# MCU.net
KiCad netlist of a schematic drawn in Altium Designer
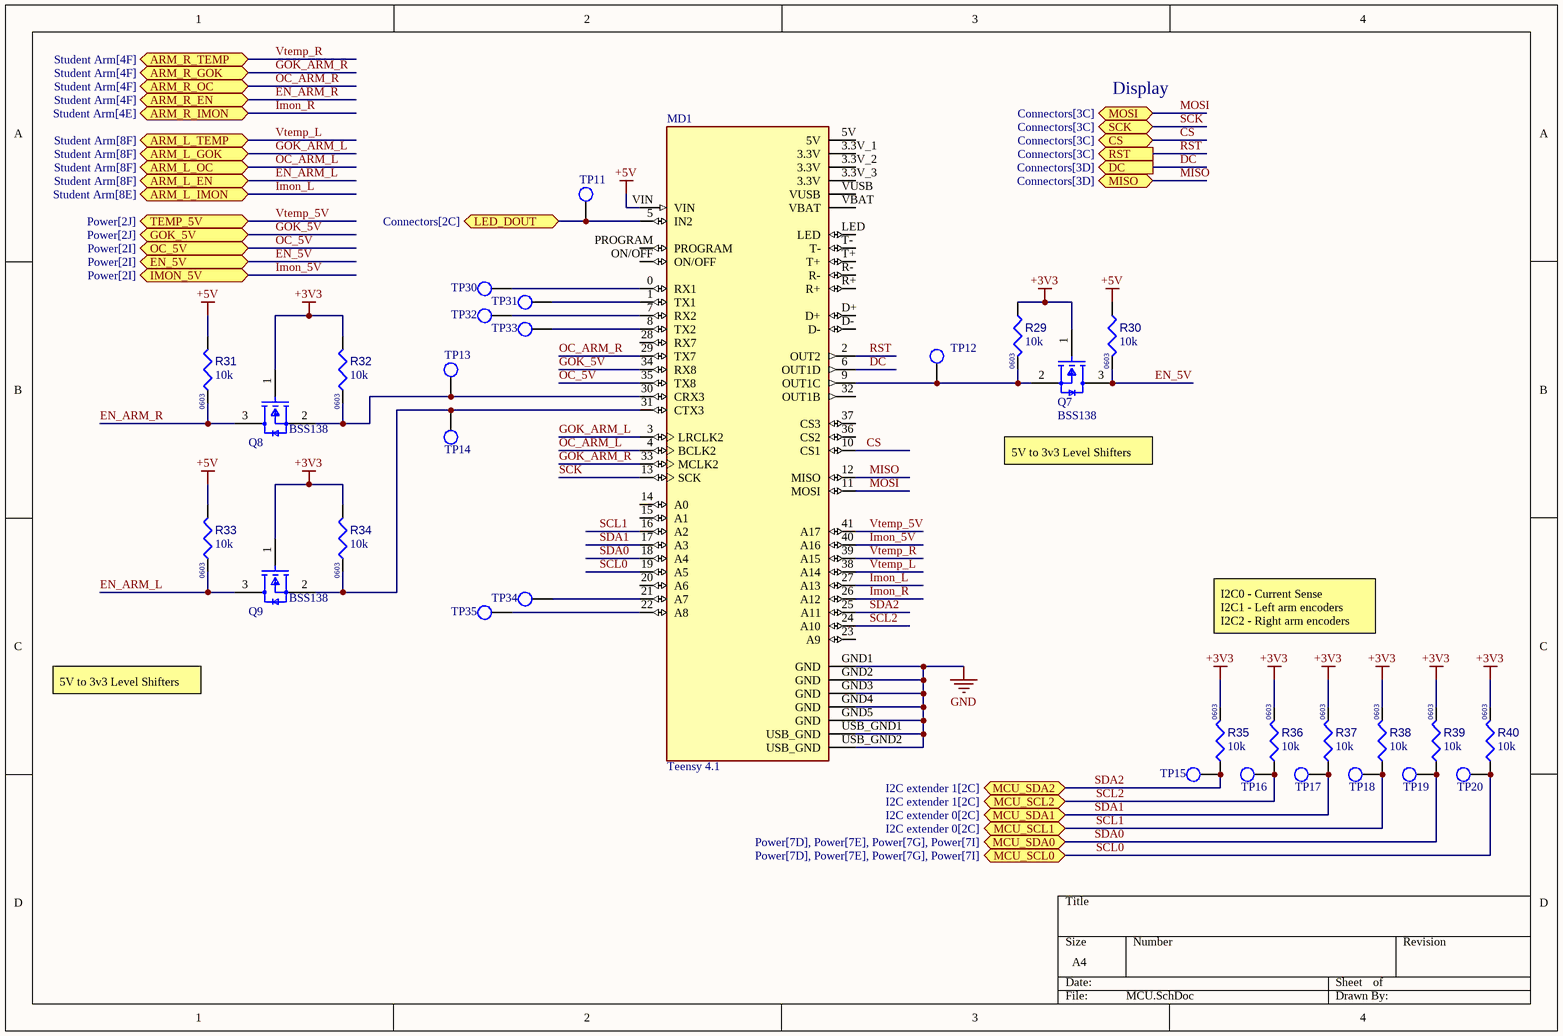
[diagram p0: MCU.SchDoc]

(export (version "E")
  (design (tool "Eeschema 10.0.6"))
  (components
    (comp (ref "MD1")
      (value "Teensy 4.1")
      (footprint "FP-DEV-16771-MFG")
      (description "iMXRT1062 Microcontroller Development Board 600MHz CPU 1GB RAM 8MB Flash")
      (libsource (lib "hawaiirobotics") (part "db1e865d41383118ef0d77a6dfc77c5"))
    )
    (comp (ref "Q7")
      (value "BSS138")
      (footprint "FP-318-08-IPC_B")
      (description "MOSFET N-CH 50V 220MA SOT-23")
      (libsource (lib "Altium Content Vault") (part "3b9c635fedb024a5347a57b145af9cc"))
    )
    (comp (ref "Q8")
      (value "BSS138")
      (footprint "FP-318-08-IPC_B")
      (description "MOSFET N-CH 50V 220MA SOT-23")
      (libsource (lib "Altium Content Vault") (part "3b9c635fedb024a5347a57b145af9cc"))
    )
    (comp (ref "Q9")
      (value "BSS138")
      (footprint "FP-318-08-IPC_B")
      (description "MOSFET N-CH 50V 220MA SOT-23")
      (libsource (lib "Altium Content Vault") (part "3b9c635fedb024a5347a57b145af9cc"))
    )
    (comp (ref "R29")
      (value "10k")
      (footprint "RESC1608X55X25NL10T15")
      (description "Chip Resistor, 10 KOhm, +/- 1%, 01 W, -55 to 155 degC, 0603 (1608 Metric)")
      (fields
        (field (name "CASE/PACKAGE") "0603")
        (field (name "POWER") "100mW")
        (field (name "TOLERANCE") "1%")
      )
      (libsource (lib "hawaiirobotics") (part "RES-2"))
    )
    (comp (ref "R30")
      (value "10k")
      (footprint "RESC1608X55X25NL10T15")
      (description "Chip Resistor, 10 KOhm, +/- 1%, 01 W, -55 to 155 degC, 0603 (1608 Metric)")
      (fields
        (field (name "CASE/PACKAGE") "0603")
        (field (name "POWER") "100mW")
        (field (name "TOLERANCE") "1%")
      )
      (libsource (lib "hawaiirobotics") (part "RES-2"))
    )
    (comp (ref "R31")
      (value "10k")
      (footprint "RESC1608X55X25NL10T15")
      (description "Chip Resistor, 10 KOhm, +/- 1%, 01 W, -55 to 155 degC, 0603 (1608 Metric)")
      (fields
        (field (name "CASE/PACKAGE") "0603")
        (field (name "POWER") "100mW")
        (field (name "TOLERANCE") "1%")
      )
      (libsource (lib "hawaiirobotics") (part "RES-2"))
    )
    (comp (ref "R32")
      (value "10k")
      (footprint "RESC1608X55X25NL10T15")
      (description "Chip Resistor, 10 KOhm, +/- 1%, 01 W, -55 to 155 degC, 0603 (1608 Metric)")
      (fields
        (field (name "CASE/PACKAGE") "0603")
        (field (name "POWER") "100mW")
        (field (name "TOLERANCE") "1%")
      )
      (libsource (lib "hawaiirobotics") (part "RES-2"))
    )
    (comp (ref "R33")
      (value "10k")
      (footprint "RESC1608X55X25NL10T15")
      (description "Chip Resistor, 10 KOhm, +/- 1%, 01 W, -55 to 155 degC, 0603 (1608 Metric)")
      (fields
        (field (name "CASE/PACKAGE") "0603")
        (field (name "POWER") "100mW")
        (field (name "TOLERANCE") "1%")
      )
      (libsource (lib "hawaiirobotics") (part "RES-2"))
    )
    (comp (ref "R34")
      (value "10k")
      (footprint "RESC1608X55X25NL10T15")
      (description "Chip Resistor, 10 KOhm, +/- 1%, 01 W, -55 to 155 degC, 0603 (1608 Metric)")
      (fields
        (field (name "CASE/PACKAGE") "0603")
        (field (name "POWER") "100mW")
        (field (name "TOLERANCE") "1%")
      )
      (libsource (lib "hawaiirobotics") (part "RES-2"))
    )
    (comp (ref "R35")
      (value "10k")
      (footprint "RESC1608X55X25NL10T15")
      (description "Chip Resistor, 10 KOhm, +/- 1%, 01 W, -55 to 155 degC, 0603 (1608 Metric)")
      (fields
        (field (name "CASE/PACKAGE") "0603")
        (field (name "POWER") "100mW")
        (field (name "TOLERANCE") "1%")
      )
      (libsource (lib "hawaiirobotics") (part "RES-2"))
    )
    (comp (ref "R36")
      (value "10k")
      (footprint "RESC1608X55X25NL10T15")
      (description "Chip Resistor, 10 KOhm, +/- 1%, 01 W, -55 to 155 degC, 0603 (1608 Metric)")
      (fields
        (field (name "CASE/PACKAGE") "0603")
        (field (name "POWER") "100mW")
        (field (name "TOLERANCE") "1%")
      )
      (libsource (lib "hawaiirobotics") (part "RES-2"))
    )
    (comp (ref "R37")
      (value "10k")
      (footprint "RESC1608X55X25NL10T15")
      (description "Chip Resistor, 10 KOhm, +/- 1%, 01 W, -55 to 155 degC, 0603 (1608 Metric)")
      (fields
        (field (name "CASE/PACKAGE") "0603")
        (field (name "POWER") "100mW")
        (field (name "TOLERANCE") "1%")
      )
      (libsource (lib "hawaiirobotics") (part "RES-2"))
    )
    (comp (ref "R38")
      (value "10k")
      (footprint "RESC1608X55X25NL10T15")
      (description "Chip Resistor, 10 KOhm, +/- 1%, 01 W, -55 to 155 degC, 0603 (1608 Metric)")
      (fields
        (field (name "CASE/PACKAGE") "0603")
        (field (name "POWER") "100mW")
        (field (name "TOLERANCE") "1%")
      )
      (libsource (lib "hawaiirobotics") (part "RES-2"))
    )
    (comp (ref "R39")
      (value "10k")
      (footprint "RESC1608X55X25NL10T15")
      (description "Chip Resistor, 10 KOhm, +/- 1%, 01 W, -55 to 155 degC, 0603 (1608 Metric)")
      (fields
        (field (name "CASE/PACKAGE") "0603")
        (field (name "POWER") "100mW")
        (field (name "TOLERANCE") "1%")
      )
      (libsource (lib "hawaiirobotics") (part "RES-2"))
    )
    (comp (ref "R40")
      (value "10k")
      (footprint "RESC1608X55X25NL10T15")
      (description "Chip Resistor, 10 KOhm, +/- 1%, 01 W, -55 to 155 degC, 0603 (1608 Metric)")
      (fields
        (field (name "CASE/PACKAGE") "0603")
        (field (name "POWER") "100mW")
        (field (name "TOLERANCE") "1%")
      )
      (libsource (lib "hawaiirobotics") (part "RES-2"))
    )
    (comp (ref "TP11")
      (value "RCUCTE")
      (footprint "FP-S2761-46R-MFG")
      (description "Test point")
      (libsource (lib "hawaiirobotics") (part "RCUCTE-Symbol-1"))
    )
    (comp (ref "TP12")
      (value "RCUCTE")
      (footprint "FP-S2761-46R-MFG")
      (description "Test point")
      (libsource (lib "hawaiirobotics") (part "RCUCTE-Symbol-1"))
    )
    (comp (ref "TP13")
      (value "RCUCTE")
      (footprint "FP-S2761-46R-MFG")
      (description "Test point")
      (libsource (lib "hawaiirobotics") (part "RCUCTE-Symbol-1"))
    )
    (comp (ref "TP14")
      (value "RCUCTE")
      (footprint "FP-S2761-46R-MFG")
      (description "Test point")
      (libsource (lib "hawaiirobotics") (part "RCUCTE-Symbol-1"))
    )
    (comp (ref "TP15")
      (value "RCUCTE")
      (footprint "FP-S2761-46R-MFG")
      (description "Test point")
      (libsource (lib "hawaiirobotics") (part "RCUCTE-Symbol-1"))
    )
    (comp (ref "TP16")
      (value "RCUCTE")
      (footprint "FP-S2761-46R-MFG")
      (description "Test point")
      (libsource (lib "hawaiirobotics") (part "RCUCTE-Symbol-1"))
    )
    (comp (ref "TP17")
      (value "RCUCTE")
      (footprint "FP-S2761-46R-MFG")
      (description "Test point")
      (libsource (lib "hawaiirobotics") (part "RCUCTE-Symbol-1"))
    )
    (comp (ref "TP18")
      (value "RCUCTE")
      (footprint "FP-S2761-46R-MFG")
      (description "Test point")
      (libsource (lib "hawaiirobotics") (part "RCUCTE-Symbol-1"))
    )
    (comp (ref "TP19")
      (value "RCUCTE")
      (footprint "FP-S2761-46R-MFG")
      (description "Test point")
      (libsource (lib "hawaiirobotics") (part "RCUCTE-Symbol-1"))
    )
    (comp (ref "TP20")
      (value "RCUCTE")
      (footprint "FP-S2761-46R-MFG")
      (description "Test point")
      (libsource (lib "hawaiirobotics") (part "RCUCTE-Symbol-1"))
    )
    (comp (ref "TP30")
      (value "RCUCTE")
      (footprint "FP-S2761-46R-MFG")
      (description "Test point")
      (libsource (lib "hawaiirobotics") (part "RCUCTE-Symbol-1"))
    )
    (comp (ref "TP31")
      (value "RCUCTE")
      (footprint "FP-S2761-46R-MFG")
      (description "Test point")
      (libsource (lib "hawaiirobotics") (part "RCUCTE-Symbol-1"))
    )
    (comp (ref "TP32")
      (value "RCUCTE")
      (footprint "FP-S2761-46R-MFG")
      (description "Test point")
      (libsource (lib "hawaiirobotics") (part "RCUCTE-Symbol-1"))
    )
    (comp (ref "TP33")
      (value "RCUCTE")
      (footprint "FP-S2761-46R-MFG")
      (description "Test point")
      (libsource (lib "hawaiirobotics") (part "RCUCTE-Symbol-1"))
    )
    (comp (ref "TP34")
      (value "RCUCTE")
      (footprint "FP-S2761-46R-MFG")
      (description "Test point")
      (libsource (lib "hawaiirobotics") (part "RCUCTE-Symbol-1"))
    )
    (comp (ref "TP35")
      (value "RCUCTE")
      (footprint "FP-S2761-46R-MFG")
      (description "Test point")
      (libsource (lib "hawaiirobotics") (part "RCUCTE-Symbol-1"))
    )
  )
  (nets
    (net (code "1") (name "+3V3") (class "Default")
      (node (ref "Q7") (pin "1") (pinfunction "G_1") (pintype "passive"))
      (node (ref "Q8") (pin "1") (pinfunction "G_1") (pintype "passive"))
      (node (ref "Q9") (pin "1") (pinfunction "G_1") (pintype "passive"))
      (node (ref "R29") (pin "2") (pinfunction "2_2") (pintype "passive"))
      (node (ref "R32") (pin "2") (pinfunction "2_2") (pintype "passive"))
      (node (ref "R34") (pin "2") (pinfunction "2_2") (pintype "passive"))
      (node (ref "R35") (pin "2") (pinfunction "2_2") (pintype "passive"))
      (node (ref "R36") (pin "2") (pinfunction "2_2") (pintype "passive"))
      (node (ref "R37") (pin "2") (pinfunction "2_2") (pintype "passive"))
      (node (ref "R38") (pin "2") (pinfunction "2_2") (pintype "passive"))
      (node (ref "R39") (pin "2") (pinfunction "2_2") (pintype "passive"))
      (node (ref "R40") (pin "2") (pinfunction "2_2") (pintype "passive"))
    )
    (net (code "2") (name "+5V") (class "Default")
      (node (ref "MD1") (pin "VIN") (pinfunction "VIN_VIN") (pintype "input"))
      (node (ref "R30") (pin "2") (pinfunction "2_2") (pintype "passive"))
      (node (ref "R31") (pin "2") (pinfunction "2_2") (pintype "passive"))
      (node (ref "R33") (pin "2") (pinfunction "2_2") (pintype "passive"))
    )
    (net (code "3") (name "/CS") (class "Default")
      (node (ref "MD1") (pin "10") (pinfunction "CS1_10") (pintype "bidirectional"))
    )
    (net (code "4") (name "/DC") (class "Default")
      (node (ref "MD1") (pin "6") (pinfunction "OUT1D_6") (pintype "output"))
    )
    (net (code "5") (name "/EN_5V") (class "Default")
      (node (ref "Q7") (pin "3") (pinfunction "D_3") (pintype "passive"))
      (node (ref "R30") (pin "1") (pinfunction "1_1") (pintype "passive"))
    )
    (net (code "6") (name "/EN_ARM_L") (class "Default")
      (node (ref "Q9") (pin "3") (pinfunction "D_3") (pintype "passive"))
      (node (ref "R33") (pin "1") (pinfunction "1_1") (pintype "passive"))
    )
    (net (code "7") (name "/EN_ARM_R") (class "Default")
      (node (ref "Q8") (pin "3") (pinfunction "D_3") (pintype "passive"))
      (node (ref "R31") (pin "1") (pinfunction "1_1") (pintype "passive"))
    )
    (net (code "8") (name "/GOK_5V") (class "Default")
      (node (ref "MD1") (pin "34") (pinfunction "RX8_34") (pintype "bidirectional"))
    )
    (net (code "9") (name "/GOK_ARM_L") (class "Default")
      (node (ref "MD1") (pin "3") (pinfunction "LRCLK2_3") (pintype "bidirectional"))
    )
    (net (code "10") (name "/GOK_ARM_R") (class "Default")
      (node (ref "MD1") (pin "33") (pinfunction "MCLK2_33") (pintype "bidirectional"))
    )
    (net (code "11") (name "/Imon_5V") (class "Default")
      (node (ref "MD1") (pin "40") (pinfunction "A16_40") (pintype "bidirectional"))
    )
    (net (code "12") (name "/Imon_L") (class "Default")
      (node (ref "MD1") (pin "27") (pinfunction "A13_27") (pintype "bidirectional"))
    )
    (net (code "13") (name "/Imon_R") (class "Default")
      (node (ref "MD1") (pin "26") (pinfunction "A12_26") (pintype "bidirectional"))
    )
    (net (code "14") (name "/LED_DOUT") (class "Default")
      (node (ref "MD1") (pin "5") (pinfunction "IN2_5") (pintype "bidirectional"))
      (node (ref "TP11") (pin "1") (pinfunction "1_1") (pintype "passive"))
    )
    (net (code "15") (name "/MISO") (class "Default")
      (node (ref "MD1") (pin "12") (pinfunction "MISO_12") (pintype "bidirectional"))
    )
    (net (code "16") (name "/MOSI") (class "Default")
      (node (ref "MD1") (pin "11") (pinfunction "MOSI_11") (pintype "bidirectional"))
    )
    (net (code "17") (name "/OC_5V") (class "Default")
      (node (ref "MD1") (pin "35") (pinfunction "TX8_35") (pintype "bidirectional"))
    )
    (net (code "18") (name "/OC_ARM_L") (class "Default")
      (node (ref "MD1") (pin "4") (pinfunction "BCLK2_4") (pintype "bidirectional"))
    )
    (net (code "19") (name "/OC_ARM_R") (class "Default")
      (node (ref "MD1") (pin "29") (pinfunction "TX7_29") (pintype "bidirectional"))
    )
    (net (code "20") (name "/RST") (class "Default")
      (node (ref "MD1") (pin "2") (pinfunction "OUT2_2") (pintype "output"))
    )
    (net (code "21") (name "/SCK") (class "Default")
      (node (ref "MD1") (pin "13") (pinfunction "SCK_13") (pintype "bidirectional"))
    )
    (net (code "22") (name "/SCL0") (class "Default")
      (node (ref "MD1") (pin "19") (pinfunction "A5_19") (pintype "bidirectional"))
      (node (ref "R40") (pin "1") (pinfunction "1_1") (pintype "passive"))
      (node (ref "TP20") (pin "1") (pinfunction "1_1") (pintype "passive"))
    )
    (net (code "23") (name "/SCL1") (class "Default")
      (node (ref "MD1") (pin "16") (pinfunction "A2_16") (pintype "bidirectional"))
      (node (ref "R38") (pin "1") (pinfunction "1_1") (pintype "passive"))
      (node (ref "TP18") (pin "1") (pinfunction "1_1") (pintype "passive"))
    )
    (net (code "24") (name "/SCL2") (class "Default")
      (node (ref "MD1") (pin "24") (pinfunction "A10_24") (pintype "bidirectional"))
      (node (ref "R36") (pin "1") (pinfunction "1_1") (pintype "passive"))
      (node (ref "TP16") (pin "1") (pinfunction "1_1") (pintype "passive"))
    )
    (net (code "25") (name "/SDA0") (class "Default")
      (node (ref "MD1") (pin "18") (pinfunction "A4_18") (pintype "bidirectional"))
      (node (ref "R39") (pin "1") (pinfunction "1_1") (pintype "passive"))
      (node (ref "TP19") (pin "1") (pinfunction "1_1") (pintype "passive"))
    )
    (net (code "26") (name "/SDA1") (class "Default")
      (node (ref "MD1") (pin "17") (pinfunction "A3_17") (pintype "bidirectional"))
      (node (ref "R37") (pin "1") (pinfunction "1_1") (pintype "passive"))
      (node (ref "TP17") (pin "1") (pinfunction "1_1") (pintype "passive"))
    )
    (net (code "27") (name "/SDA2") (class "Default")
      (node (ref "MD1") (pin "25") (pinfunction "A11_25") (pintype "bidirectional"))
      (node (ref "R35") (pin "1") (pinfunction "1_1") (pintype "passive"))
      (node (ref "TP15") (pin "1") (pinfunction "1_1") (pintype "passive"))
    )
    (net (code "28") (name "/Vtemp_5V") (class "Default")
      (node (ref "MD1") (pin "41") (pinfunction "A17_41") (pintype "bidirectional"))
    )
    (net (code "29") (name "/Vtemp_L") (class "Default")
      (node (ref "MD1") (pin "38") (pinfunction "A14_38") (pintype "bidirectional"))
    )
    (net (code "30") (name "/Vtemp_R") (class "Default")
      (node (ref "MD1") (pin "39") (pinfunction "A15_39") (pintype "bidirectional"))
    )
    (net (code "31") (name "GND") (class "Default")
      (node (ref "MD1") (pin "GND1") (pinfunction "GND_GND1") (pintype "power_in"))
      (node (ref "MD1") (pin "GND2") (pinfunction "GND_GND2") (pintype "power_in"))
      (node (ref "MD1") (pin "GND3") (pinfunction "GND_GND3") (pintype "power_in"))
      (node (ref "MD1") (pin "GND4") (pinfunction "GND_GND4") (pintype "power_in"))
      (node (ref "MD1") (pin "GND5") (pinfunction "GND_GND5") (pintype "power_in"))
      (node (ref "MD1") (pin "USB_GND1") (pinfunction "USB_GND_USB_GND1") (pintype "power_in"))
      (node (ref "MD1") (pin "USB_GND2") (pinfunction "USB_GND_USB_GND2") (pintype "power_in"))
    )
    (net (code "32") (name "Net-(MD1-A7)") (class "Default")
      (node (ref "MD1") (pin "21") (pinfunction "A7_21") (pintype "bidirectional"))
      (node (ref "TP34") (pin "1") (pinfunction "1_1") (pintype "passive"))
    )
    (net (code "33") (name "Net-(MD1-A8)") (class "Default")
      (node (ref "MD1") (pin "22") (pinfunction "A8_22") (pintype "bidirectional"))
      (node (ref "TP35") (pin "1") (pinfunction "1_1") (pintype "passive"))
    )
    (net (code "34") (name "Net-(MD1-CRX3)") (class "Default")
      (node (ref "MD1") (pin "30") (pinfunction "CRX3_30") (pintype "bidirectional"))
      (node (ref "Q8") (pin "2") (pinfunction "S_2") (pintype "passive"))
      (node (ref "R32") (pin "1") (pinfunction "1_1") (pintype "passive"))
      (node (ref "TP13") (pin "1") (pinfunction "1_1") (pintype "passive"))
    )
    (net (code "35") (name "Net-(MD1-CTX3)") (class "Default")
      (node (ref "MD1") (pin "31") (pinfunction "CTX3_31") (pintype "bidirectional"))
      (node (ref "Q9") (pin "2") (pinfunction "S_2") (pintype "passive"))
      (node (ref "R34") (pin "1") (pinfunction "1_1") (pintype "passive"))
      (node (ref "TP14") (pin "1") (pinfunction "1_1") (pintype "passive"))
    )
    (net (code "36") (name "Net-(MD1-OUT1C)") (class "Default")
      (node (ref "MD1") (pin "9") (pinfunction "OUT1C_9") (pintype "output"))
      (node (ref "Q7") (pin "2") (pinfunction "S_2") (pintype "passive"))
      (node (ref "R29") (pin "1") (pinfunction "1_1") (pintype "passive"))
      (node (ref "TP12") (pin "1") (pinfunction "1_1") (pintype "passive"))
    )
    (net (code "37") (name "Net-(MD1-RX1)") (class "Default")
      (node (ref "MD1") (pin "0") (pinfunction "RX1_0") (pintype "bidirectional"))
      (node (ref "TP30") (pin "1") (pinfunction "1_1") (pintype "passive"))
    )
    (net (code "38") (name "Net-(MD1-RX2)") (class "Default")
      (node (ref "MD1") (pin "7") (pinfunction "RX2_7") (pintype "bidirectional"))
      (node (ref "TP32") (pin "1") (pinfunction "1_1") (pintype "passive"))
    )
    (net (code "39") (name "Net-(MD1-TX1)") (class "Default")
      (node (ref "MD1") (pin "1") (pinfunction "TX1_1") (pintype "bidirectional"))
      (node (ref "TP31") (pin "1") (pinfunction "1_1") (pintype "passive"))
    )
    (net (code "40") (name "Net-(MD1-TX2)") (class "Default")
      (node (ref "MD1") (pin "8") (pinfunction "TX2_8") (pintype "bidirectional"))
      (node (ref "TP33") (pin "1") (pinfunction "1_1") (pintype "passive"))
    )
    (net (code "41") (name "unconnected-(MD1-3.3V-Pad3.3V_1)") (class "Default")
      (node (ref "MD1") (pin "3.3V_1") (pinfunction "3.3V_3.3V_1") (pintype "power_in"))
    )
    (net (code "42") (name "unconnected-(MD1-3.3V-Pad3.3V_2)") (class "Default")
      (node (ref "MD1") (pin "3.3V_2") (pinfunction "3.3V_3.3V_2") (pintype "power_in"))
    )
    (net (code "43") (name "unconnected-(MD1-3.3V-Pad3.3V_3)") (class "Default")
      (node (ref "MD1") (pin "3.3V_3") (pinfunction "3.3V_3.3V_3") (pintype "power_in"))
    )
    (net (code "44") (name "unconnected-(MD1-A0-Pad14)") (class "Default")
      (node (ref "MD1") (pin "14") (pinfunction "A0_14") (pintype "bidirectional"))
    )
    (net (code "45") (name "unconnected-(MD1-A1-Pad15)") (class "Default")
      (node (ref "MD1") (pin "15") (pinfunction "A1_15") (pintype "bidirectional"))
    )
    (net (code "46") (name "unconnected-(MD1-A6-Pad20)") (class "Default")
      (node (ref "MD1") (pin "20") (pinfunction "A6_20") (pintype "bidirectional"))
    )
    (net (code "47") (name "unconnected-(MD1-A9-Pad23)") (class "Default")
      (node (ref "MD1") (pin "23") (pinfunction "A9_23") (pintype "bidirectional"))
    )
    (net (code "48") (name "unconnected-(MD1-CS2-Pad36)") (class "Default")
      (node (ref "MD1") (pin "36") (pinfunction "CS2_36") (pintype "bidirectional"))
    )
    (net (code "49") (name "unconnected-(MD1-CS3-Pad37)") (class "Default")
      (node (ref "MD1") (pin "37") (pinfunction "CS3_37") (pintype "bidirectional"))
    )
    (net (code "50") (name "unconnected-(MD1-OUT1B-Pad32)") (class "Default")
      (node (ref "MD1") (pin "32") (pinfunction "OUT1B_32") (pintype "output"))
    )
    (net (code "51") (name "unconnected-(MD1-Pad5V)") (class "Default")
      (node (ref "MD1") (pin "5V") (pinfunction "5V_5V") (pintype "power_in"))
    )
    (net (code "52") (name "unconnected-(MD1-PadD+)") (class "Default")
      (node (ref "MD1") (pin "D+") (pinfunction "D+_D+") (pintype "bidirectional"))
    )
    (net (code "53") (name "unconnected-(MD1-PadD-)") (class "Default")
      (node (ref "MD1") (pin "D-") (pinfunction "D-_D-") (pintype "bidirectional"))
    )
    (net (code "54") (name "unconnected-(MD1-PadLED)") (class "Default")
      (node (ref "MD1") (pin "LED") (pinfunction "LED_LED") (pintype "bidirectional"))
    )
    (net (code "55") (name "unconnected-(MD1-PadON{slash}OFF)") (class "Default")
      (node (ref "MD1") (pin "ON/OFF") (pinfunction "ON/OFF_ON/OFF") (pintype "bidirectional"))
    )
    (net (code "56") (name "unconnected-(MD1-PadPROGRAM)") (class "Default")
      (node (ref "MD1") (pin "PROGRAM") (pinfunction "PROGRAM_PROGRAM") (pintype "bidirectional"))
    )
    (net (code "57") (name "unconnected-(MD1-PadR+)") (class "Default")
      (node (ref "MD1") (pin "R+") (pinfunction "R+_R+") (pintype "bidirectional"))
    )
    (net (code "58") (name "unconnected-(MD1-PadR-)") (class "Default")
      (node (ref "MD1") (pin "R-") (pinfunction "R-_R-") (pintype "bidirectional"))
    )
    (net (code "59") (name "unconnected-(MD1-PadT+)") (class "Default")
      (node (ref "MD1") (pin "T+") (pinfunction "T+_T+") (pintype "bidirectional"))
    )
    (net (code "60") (name "unconnected-(MD1-PadT-)") (class "Default")
      (node (ref "MD1") (pin "T-") (pinfunction "T-_T-") (pintype "bidirectional"))
    )
    (net (code "61") (name "unconnected-(MD1-PadVBAT)") (class "Default")
      (node (ref "MD1") (pin "VBAT") (pinfunction "VBAT_VBAT") (pintype "passive"))
    )
    (net (code "62") (name "unconnected-(MD1-PadVUSB)") (class "Default")
      (node (ref "MD1") (pin "VUSB") (pinfunction "VUSB_VUSB") (pintype "passive"))
    )
    (net (code "63") (name "unconnected-(MD1-RX7-Pad28)") (class "Default")
      (node (ref "MD1") (pin "28") (pinfunction "RX7_28") (pintype "bidirectional"))
    )
  )
)
